# schematicNew.net
KiCad netlist of a schematic drawn in EAGLE
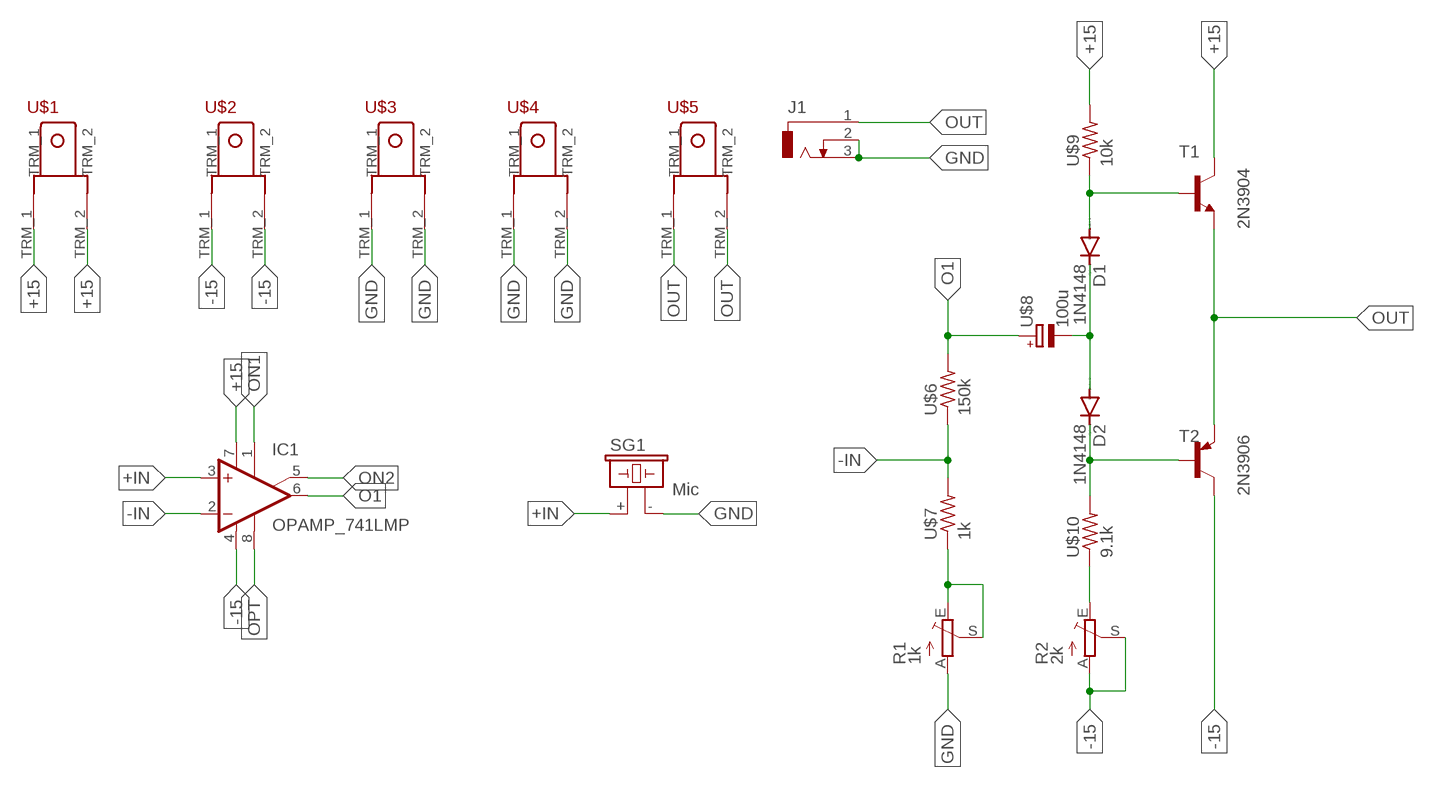
[diagram p0: schematic, sheet 1]

(export (version "E")
  (design (tool "Eeschema 10.0.6"))
  (components
    (comp (ref "D1")
      (value "1N4148")
      (footprint "eagle-import:DO35-10")
      (libsource (lib "eagle-import") (part "1N4148DO35-10"))
    )
    (comp (ref "D2")
      (value "1N4148")
      (footprint "eagle-import:DO35-10")
      (libsource (lib "eagle-import") (part "1N4148DO35-10"))
    )
    (comp (ref "IC1")
      (value "OPAMP_741LMP")
      (footprint "eagle-import:DIL08")
      (libsource (lib "eagle-import") (part "OPAMP_741PLM"))
    )
    (comp (ref "J1")
      (value "CON_JACK")
      (footprint "eagle-import:DCJ0303")
      (libsource (lib "eagle-import") (part "CON_JACK"))
    )
    (comp (ref "R1")
      (value "1k")
      (footprint "eagle-import:CA6V")
      (libsource (lib "eagle-import") (part "TRIM_EU-CA6V"))
    )
    (comp (ref "R2")
      (value "2k")
      (footprint "eagle-import:CA6V")
      (libsource (lib "eagle-import") (part "TRIM_EU-CA6V"))
    )
    (comp (ref "SG1")
      (value "Mic")
      (footprint "eagle-import:F_CM12P")
      (libsource (lib "eagle-import") (part "BUZZER"))
    )
    (comp (ref "T1")
      (value "2N3904")
      (footprint "eagle-import:TO92-EBC")
      (libsource (lib "eagle-import") (part "-NPN-TO92-EBC2N3904"))
    )
    (comp (ref "T2")
      (value "2N3906")
      (footprint "eagle-import:TO92-EBC")
      (libsource (lib "eagle-import") (part "-PNP-TO92-EBC2N3906"))
    )
    (comp (ref "U$1")
      (value "TERMINAL_EDITED")
      (footprint "eagle-import:TERMINAL_EDITED")
      (libsource (lib "eagle-import") (part "TERMINAL_EDITED"))
    )
    (comp (ref "U$2")
      (value "TERMINAL_EDITED")
      (footprint "eagle-import:TERMINAL_EDITED")
      (libsource (lib "eagle-import") (part "TERMINAL_EDITED"))
    )
    (comp (ref "U$3")
      (value "TERMINAL_EDITED")
      (footprint "eagle-import:TERMINAL_EDITED")
      (libsource (lib "eagle-import") (part "TERMINAL_EDITED"))
    )
    (comp (ref "U$4")
      (value "TERMINAL_EDITED")
      (footprint "eagle-import:TERMINAL_EDITED")
      (libsource (lib "eagle-import") (part "TERMINAL_EDITED"))
    )
    (comp (ref "U$5")
      (value "TERMINAL_EDITED")
      (footprint "eagle-import:TERMINAL_EDITED")
      (libsource (lib "eagle-import") (part "TERMINAL_EDITED"))
    )
    (comp (ref "U$6")
      (value "150k")
      (footprint "eagle-import:0204_7")
      (libsource (lib "eagle-import") (part "RES-7"))
    )
    (comp (ref "U$7")
      (value "1k")
      (footprint "eagle-import:0204_7")
      (libsource (lib "eagle-import") (part "RES-7"))
    )
    (comp (ref "U$8")
      (value "100u")
      (footprint "eagle-import:E3,5-8")
      (libsource (lib "eagle-import") (part "CAP_POL"))
    )
    (comp (ref "U$9")
      (value "10k")
      (footprint "eagle-import:0204_7")
      (libsource (lib "eagle-import") (part "RES-7"))
    )
    (comp (ref "U$10")
      (value "9.1k")
      (footprint "eagle-import:0204_7")
      (libsource (lib "eagle-import") (part "RES-7"))
    )
  )
  (nets
    (net (code "1") (name "+15") (class "Default")
      (node (ref "IC1") (pin "7") (pinfunction "V+_7") (pintype "power_in"))
      (node (ref "T1") (pin "C") (pinfunction "C_C") (pintype "passive"))
      (node (ref "U$1") (pin "TRM_1") (pinfunction "TRM_1_TRM_1") (pintype "bidirectional"))
      (node (ref "U$1") (pin "TRM_2") (pinfunction "TRM_2_TRM_2") (pintype "bidirectional"))
      (node (ref "U$9") (pin "2") (pinfunction "2_2") (pintype "passive"))
    )
    (net (code "2") (name "+IN") (class "Default")
      (node (ref "IC1") (pin "3") (pinfunction "+IN_3") (pintype "input"))
      (node (ref "SG1") (pin "+") (pinfunction "1_+") (pintype "passive"))
    )
    (net (code "3") (name "-15") (class "Default")
      (node (ref "IC1") (pin "4") (pinfunction "V-_4") (pintype "power_in"))
      (node (ref "R2") (pin "A") (pinfunction "A_A") (pintype "passive"))
      (node (ref "R2") (pin "S") (pinfunction "S_S") (pintype "passive"))
      (node (ref "T2") (pin "C") (pinfunction "C_C") (pintype "passive"))
      (node (ref "U$2") (pin "TRM_1") (pinfunction "TRM_1_TRM_1") (pintype "bidirectional"))
      (node (ref "U$2") (pin "TRM_2") (pinfunction "TRM_2_TRM_2") (pintype "bidirectional"))
    )
    (net (code "4") (name "-IN") (class "Default")
      (node (ref "IC1") (pin "2") (pinfunction "-IN_2") (pintype "input"))
      (node (ref "U$6") (pin "1") (pinfunction "1_1") (pintype "passive"))
      (node (ref "U$7") (pin "2") (pinfunction "2_2") (pintype "passive"))
    )
    (net (code "5") (name "GND") (class "Default")
      (node (ref "J1") (pin "2") (pinfunction "2_2") (pintype "passive"))
      (node (ref "J1") (pin "3") (pinfunction "3_3") (pintype "passive"))
      (node (ref "R1") (pin "A") (pinfunction "A_A") (pintype "passive"))
      (node (ref "SG1") (pin "-") (pinfunction "2_-") (pintype "passive"))
      (node (ref "U$3") (pin "TRM_1") (pinfunction "TRM_1_TRM_1") (pintype "bidirectional"))
      (node (ref "U$3") (pin "TRM_2") (pinfunction "TRM_2_TRM_2") (pintype "bidirectional"))
      (node (ref "U$4") (pin "TRM_1") (pinfunction "TRM_1_TRM_1") (pintype "bidirectional"))
      (node (ref "U$4") (pin "TRM_2") (pinfunction "TRM_2_TRM_2") (pintype "bidirectional"))
    )
    (net (code "6") (name "Net-(D1-PadA)") (class "Default")
      (node (ref "D1") (pin "A") (pinfunction "A_A") (pintype "passive"))
      (node (ref "T1") (pin "B") (pinfunction "B_B") (pintype "passive"))
      (node (ref "U$9") (pin "1") (pinfunction "1_1") (pintype "passive"))
    )
    (net (code "7") (name "Net-(D1-PadC)") (class "Default")
      (node (ref "D1") (pin "C") (pinfunction "C_C") (pintype "passive"))
      (node (ref "D2") (pin "A") (pinfunction "A_A") (pintype "passive"))
      (node (ref "U$8") (pin "-") (pinfunction "-_-") (pintype "passive"))
    )
    (net (code "8") (name "Net-(D2-PadC)") (class "Default")
      (node (ref "D2") (pin "C") (pinfunction "C_C") (pintype "passive"))
      (node (ref "T2") (pin "B") (pinfunction "B_B") (pintype "passive"))
      (node (ref "U$10") (pin "2") (pinfunction "2_2") (pintype "passive"))
    )
    (net (code "9") (name "Net-(R1-PadE)") (class "Default")
      (node (ref "R1") (pin "E") (pinfunction "E_E") (pintype "passive"))
      (node (ref "R1") (pin "S") (pinfunction "S_S") (pintype "passive"))
      (node (ref "U$7") (pin "1") (pinfunction "1_1") (pintype "passive"))
    )
    (net (code "10") (name "Net-(R2-PadE)") (class "Default")
      (node (ref "R2") (pin "E") (pinfunction "E_E") (pintype "passive"))
      (node (ref "U$10") (pin "1") (pinfunction "1_1") (pintype "passive"))
    )
    (net (code "11") (name "O1") (class "Default")
      (node (ref "IC1") (pin "6") (pinfunction "OUT_6") (pintype "output"))
      (node (ref "U$6") (pin "2") (pinfunction "2_2") (pintype "passive"))
      (node (ref "U$8") (pin "+") (pinfunction "+_+") (pintype "passive"))
    )
    (net (code "12") (name "ON1") (class "Default")
      (node (ref "IC1") (pin "1") (pinfunction "ON1_1") (pintype "passive"))
    )
    (net (code "13") (name "ON2") (class "Default")
      (node (ref "IC1") (pin "5") (pinfunction "ON2_5") (pintype "passive"))
    )
    (net (code "14") (name "OPT") (class "Default")
      (node (ref "IC1") (pin "8") (pinfunction "OPT_8") (pintype "passive"))
    )
    (net (code "15") (name "OUT") (class "Default")
      (node (ref "J1") (pin "1") (pinfunction "1_1") (pintype "passive"))
      (node (ref "T1") (pin "E") (pinfunction "E_E") (pintype "passive"))
      (node (ref "T2") (pin "E") (pinfunction "E_E") (pintype "passive"))
      (node (ref "U$5") (pin "TRM_1") (pinfunction "TRM_1_TRM_1") (pintype "bidirectional"))
      (node (ref "U$5") (pin "TRM_2") (pinfunction "TRM_2_TRM_2") (pintype "bidirectional"))
    )
  )
)
